# rs232-TTL.net
KiCad netlist of a schematic drawn in EAGLE
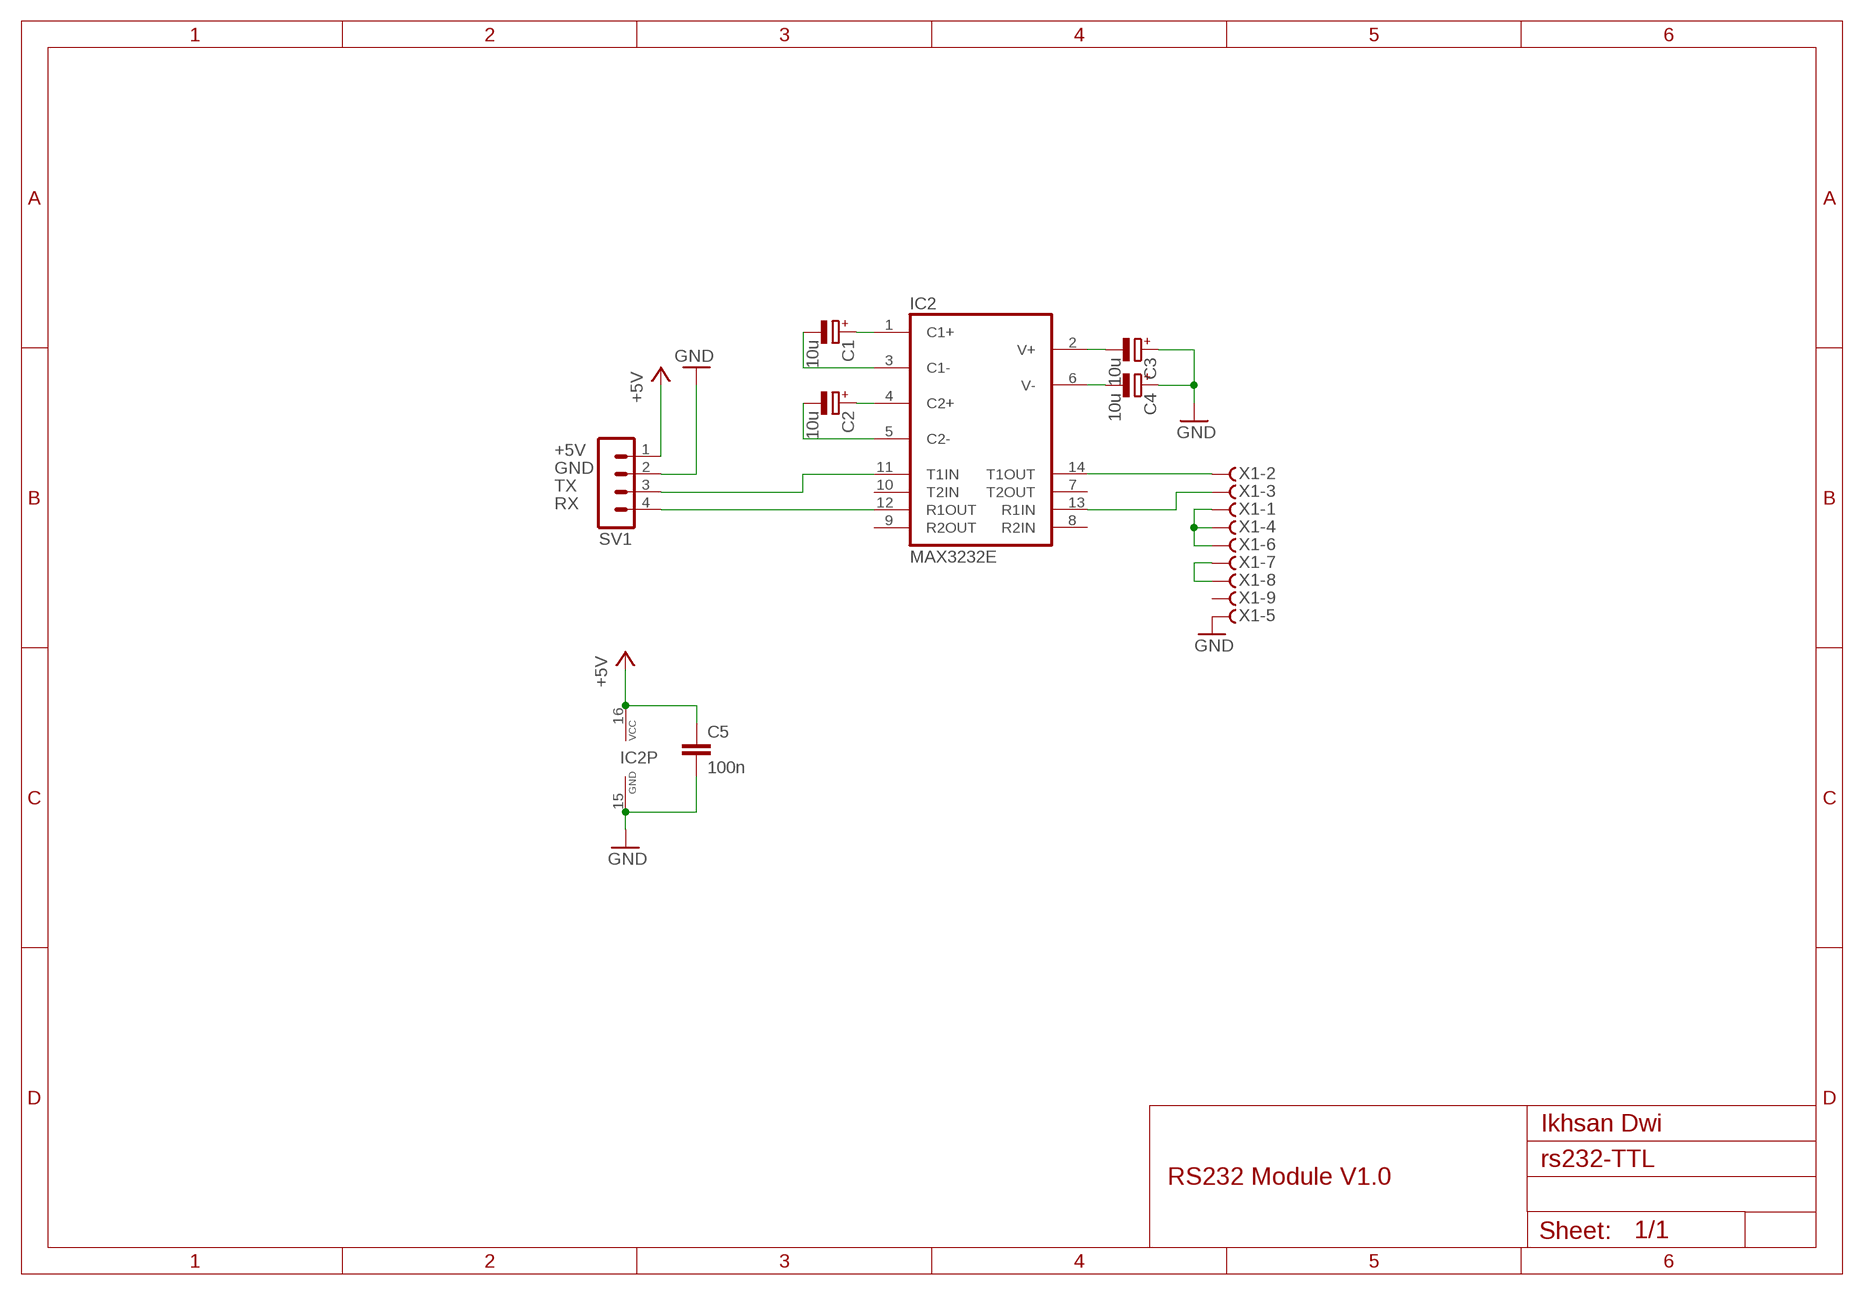
[diagram p0: schematic, sheet 1]

(export (version "E")
  (design (tool "Eeschema 10.0.6"))
  (components
    (comp (ref "C1")
      (value "10u")
      (footprint "eagle-import:E2,5-6")
      (libsource (lib "eagle-import") (part "CPOL-EUE2.5-6"))
    )
    (comp (ref "C2")
      (value "10u")
      (footprint "eagle-import:E2,5-6")
      (libsource (lib "eagle-import") (part "CPOL-EUE2.5-6"))
    )
    (comp (ref "C3")
      (value "10u")
      (footprint "eagle-import:E2,5-6")
      (libsource (lib "eagle-import") (part "CPOL-EUE2.5-6"))
    )
    (comp (ref "C4")
      (value "10u")
      (footprint "eagle-import:E2,5-6")
      (libsource (lib "eagle-import") (part "CPOL-EUE2.5-6"))
    )
    (comp (ref "C5")
      (value "100n")
      (footprint "eagle-import:C050-024X044")
      (libsource (lib "eagle-import") (part "C-EU050-024X044"))
    )
    (comp (ref "IC2")
      (value "MAX3232E")
      (footprint "eagle-import:DIL16")
      (libsource (lib "eagle-import") (part "MAX232"))
    )
    (comp (ref "SV1")
      (value "MA04-1")
      (footprint "eagle-import:MA04-1")
      (libsource (lib "eagle-import") (part "MA04-1"))
    )
    (comp (ref "X1")
      (value "F09HS")
      (footprint "eagle-import:F09H")
      (libsource (lib "eagle-import") (part "F09HS"))
    )
  )
  (nets
    (net (code "1") (name "+5V") (class "Default")
      (node (ref "C5") (pin "1") (pinfunction "1_1") (pintype "passive"))
      (node (ref "IC2") (pin "16") (pinfunction "VCC_16") (pintype "power_in"))
      (node (ref "SV1") (pin "1") (pinfunction "1_1") (pintype "passive"))
    )
    (net (code "2") (name "/RX") (class "Default")
      (node (ref "IC2") (pin "12") (pinfunction "R1OUT_12") (pintype "output"))
      (node (ref "SV1") (pin "4") (pinfunction "4_4") (pintype "passive"))
    )
    (net (code "3") (name "/TX") (class "Default")
      (node (ref "IC2") (pin "11") (pinfunction "T1IN_11") (pintype "input"))
      (node (ref "SV1") (pin "3") (pinfunction "3_3") (pintype "passive"))
    )
    (net (code "4") (name "GND") (class "Default")
      (node (ref "C3") (pin "+") (pinfunction "+_+") (pintype "passive"))
      (node (ref "C4") (pin "+") (pinfunction "+_+") (pintype "passive"))
      (node (ref "C5") (pin "2") (pinfunction "2_2") (pintype "passive"))
      (node (ref "IC2") (pin "15") (pinfunction "GND_15") (pintype "power_in"))
      (node (ref "SV1") (pin "2") (pinfunction "2_2") (pintype "passive"))
      (node (ref "X1") (pin "5") (pinfunction "F_5") (pintype "passive"))
    )
    (net (code "5") (name "Net-(IC2A-C1+)") (class "Default")
      (node (ref "C1") (pin "+") (pinfunction "+_+") (pintype "passive"))
      (node (ref "IC2") (pin "1") (pinfunction "C1+_1") (pintype "bidirectional"))
    )
    (net (code "6") (name "Net-(IC2A-C1-)") (class "Default")
      (node (ref "C1") (pin "-") (pinfunction "-_-") (pintype "passive"))
      (node (ref "IC2") (pin "3") (pinfunction "C1-_3") (pintype "bidirectional"))
    )
    (net (code "7") (name "Net-(IC2A-C2+)") (class "Default")
      (node (ref "C2") (pin "+") (pinfunction "+_+") (pintype "passive"))
      (node (ref "IC2") (pin "4") (pinfunction "C2+_4") (pintype "bidirectional"))
    )
    (net (code "8") (name "Net-(IC2A-C2-)") (class "Default")
      (node (ref "C2") (pin "-") (pinfunction "-_-") (pintype "passive"))
      (node (ref "IC2") (pin "5") (pinfunction "C2-_5") (pintype "bidirectional"))
    )
    (net (code "9") (name "Net-(IC2A-R1IN)") (class "Default")
      (node (ref "IC2") (pin "13") (pinfunction "R1IN_13") (pintype "input"))
      (node (ref "X1") (pin "3") (pinfunction "F_3") (pintype "passive"))
    )
    (net (code "10") (name "Net-(IC2A-T1OUT)") (class "Default")
      (node (ref "IC2") (pin "14") (pinfunction "T1OUT_14") (pintype "output"))
      (node (ref "X1") (pin "2") (pinfunction "F_2") (pintype "passive"))
    )
    (net (code "11") (name "Net-(IC2A-V+)") (class "Default")
      (node (ref "C3") (pin "-") (pinfunction "-_-") (pintype "passive"))
      (node (ref "IC2") (pin "2") (pinfunction "V+_2") (pintype "bidirectional"))
    )
    (net (code "12") (name "Net-(IC2A-V-)") (class "Default")
      (node (ref "C4") (pin "-") (pinfunction "-_-") (pintype "passive"))
      (node (ref "IC2") (pin "6") (pinfunction "V-_6") (pintype "bidirectional"))
    )
    (net (code "13") (name "Net-(X1A-F)") (class "Default")
      (node (ref "X1") (pin "1") (pinfunction "F_1") (pintype "passive"))
      (node (ref "X1") (pin "4") (pinfunction "F_4") (pintype "passive"))
      (node (ref "X1") (pin "6") (pinfunction "F_6") (pintype "passive"))
    )
    (net (code "14") (name "Net-(X1G-F)") (class "Default")
      (node (ref "X1") (pin "7") (pinfunction "F_7") (pintype "passive"))
      (node (ref "X1") (pin "8") (pinfunction "F_8") (pintype "passive"))
    )
    (net (code "15") (name "unconnected-(IC2A-R2IN-Pad8)") (class "Default")
      (node (ref "IC2") (pin "8") (pinfunction "R2IN_8") (pintype "input"))
    )
    (net (code "16") (name "unconnected-(IC2A-R2OUT-Pad9)") (class "Default")
      (node (ref "IC2") (pin "9") (pinfunction "R2OUT_9") (pintype "output"))
    )
    (net (code "17") (name "unconnected-(IC2A-T2IN-Pad10)") (class "Default")
      (node (ref "IC2") (pin "10") (pinfunction "T2IN_10") (pintype "input"))
    )
    (net (code "18") (name "unconnected-(IC2A-T2OUT-Pad7)") (class "Default")
      (node (ref "IC2") (pin "7") (pinfunction "T2OUT_7") (pintype "output"))
    )
    (net (code "19") (name "unconnected-(X1I-F-Pad9)") (class "Default")
      (node (ref "X1") (pin "9") (pinfunction "F_9") (pintype "passive"))
    )
  )
)
